# GEOF_MainBoard.net
KiCad netlist of a schematic drawn in EasyEDA Pro
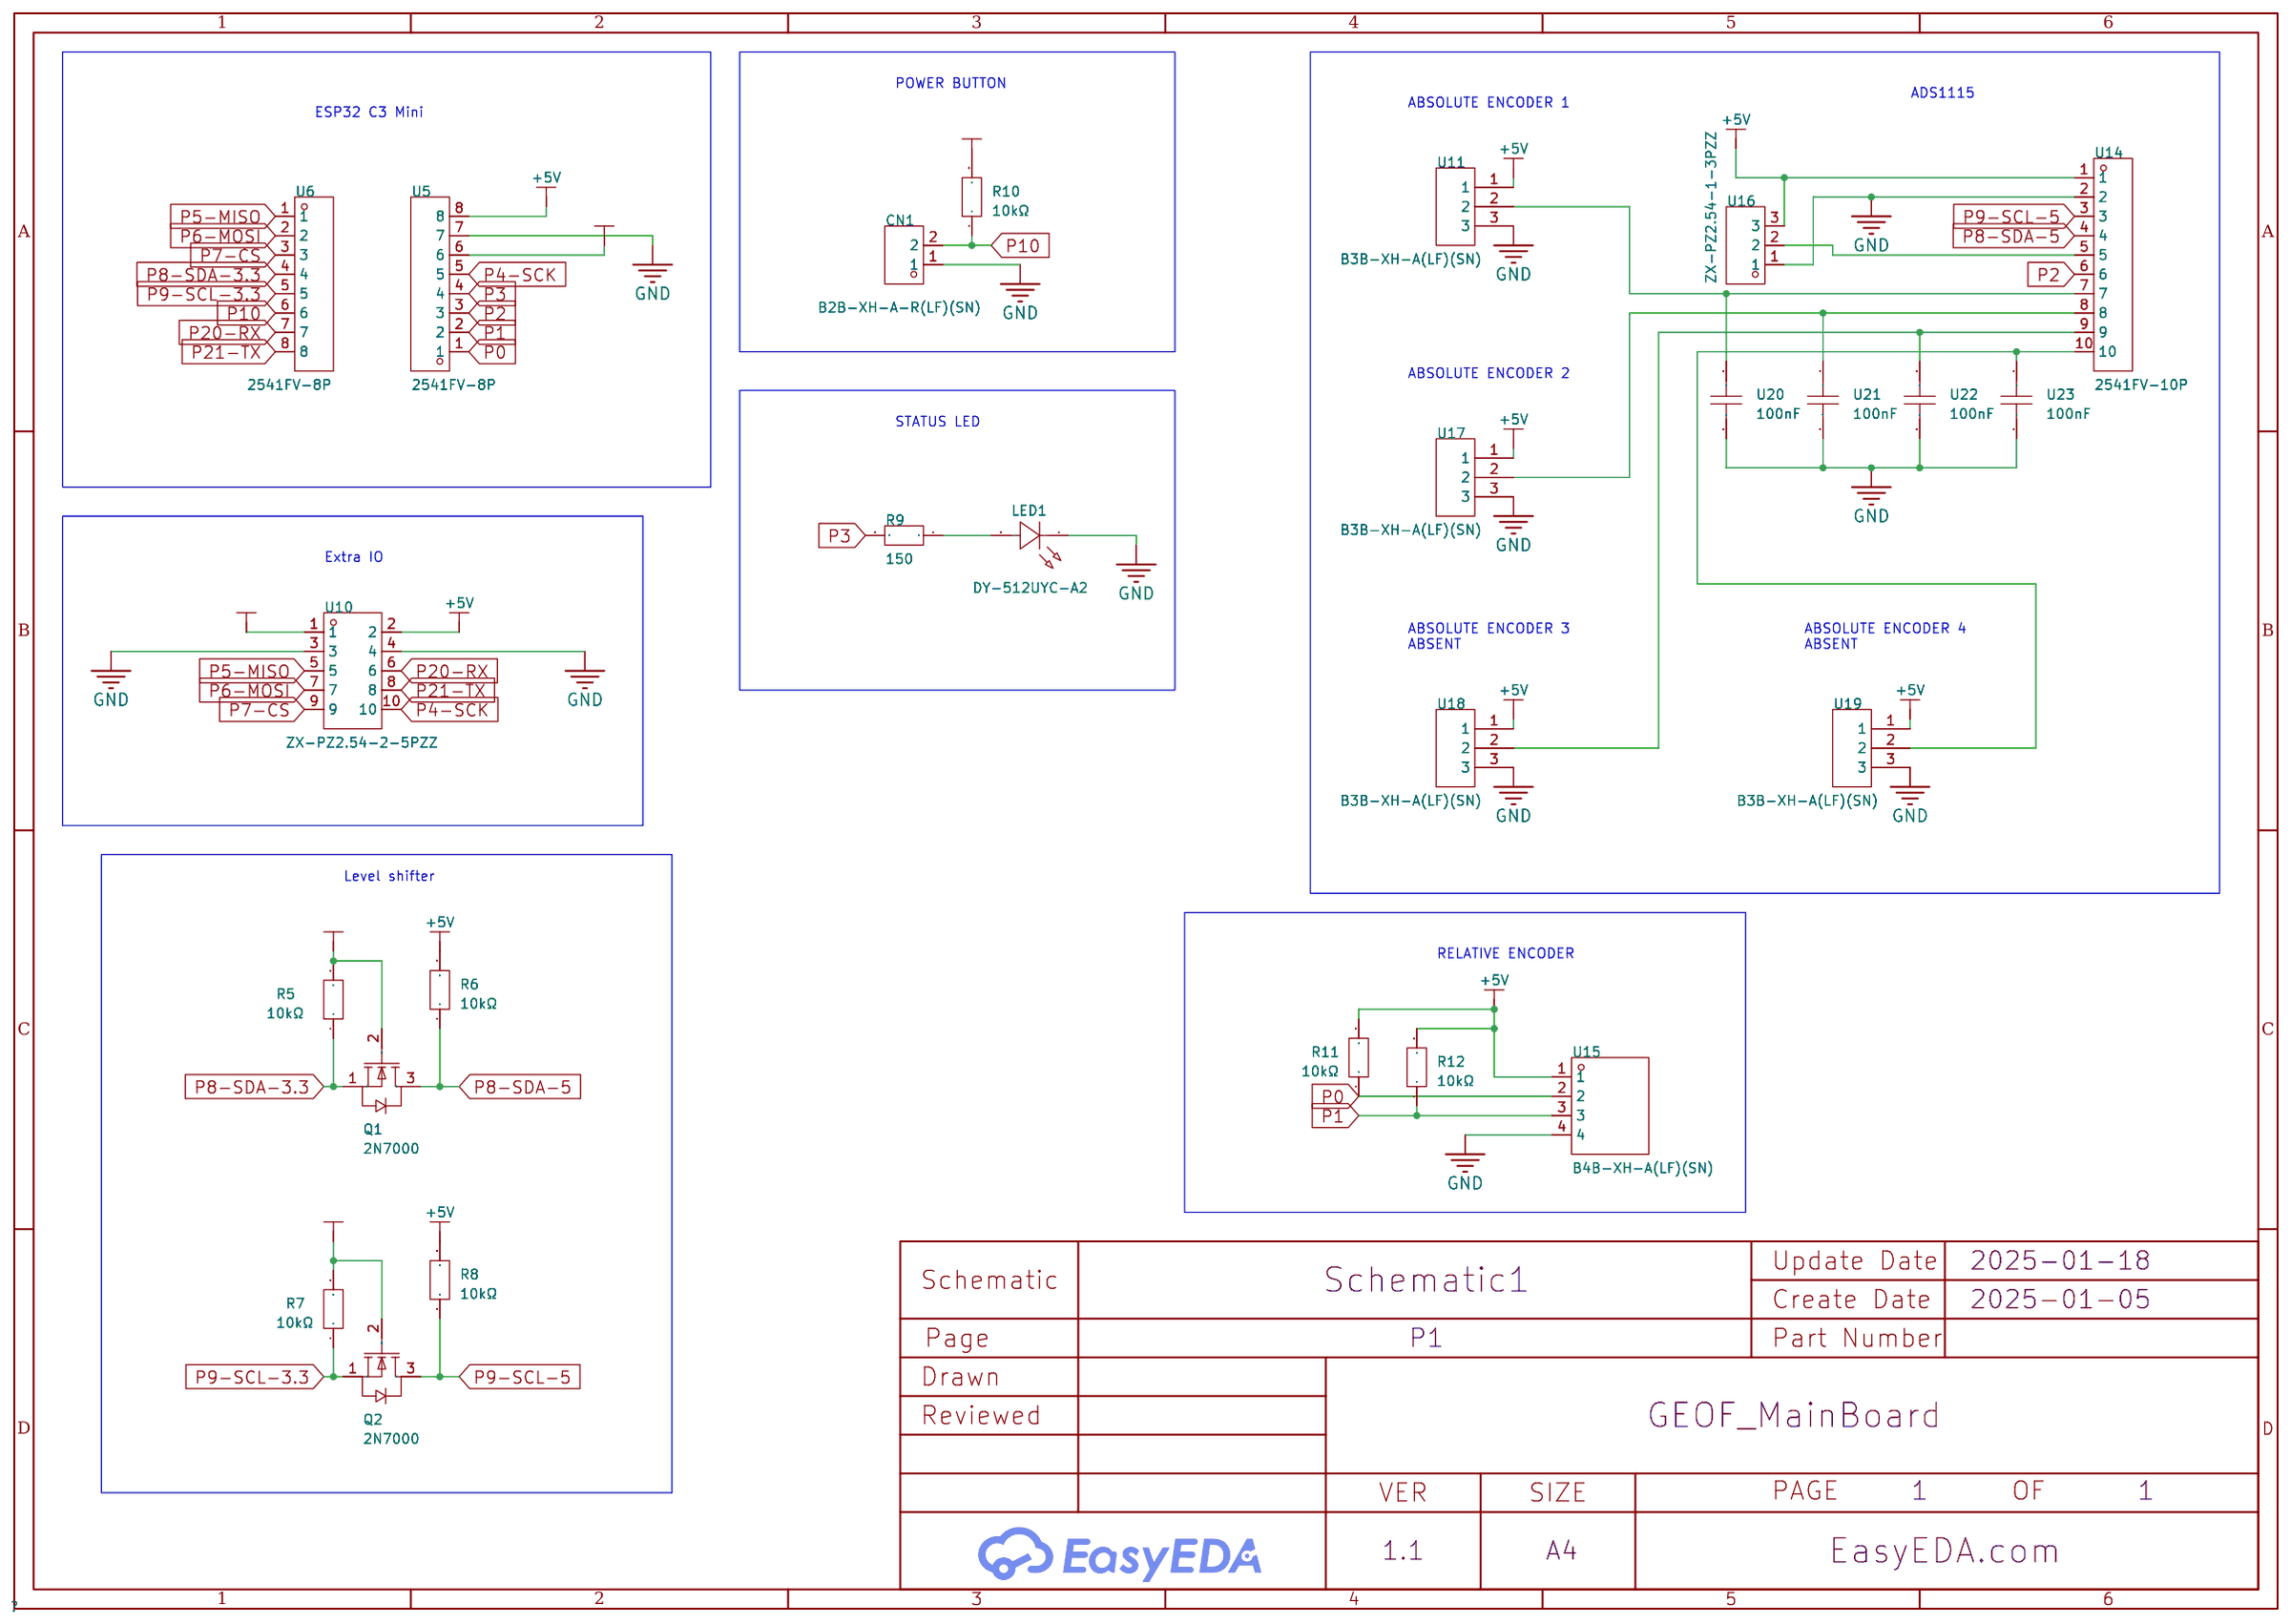
[diagram p0: schematic sheet]

(export (version "E")
  (design (tool "Eeschema 10.0.6"))
  (components
    (comp (ref "CN1")
      (value "B2B-XH-A-R(LF)(SN)")
      (footprint "easyedapro:CONN-TH_B2B-XH-A")
      (fields (field (name "Manufacturer") "JST"))
      (libsource (lib "easyedapro") (part "B2B-XH-A-R(LF)(SN)"))
    )
    (comp (ref "LED1")
      (value "DY-512UYC-A2")
      (footprint "easyedapro:LED-TH_L3.2-W2.0-P2.54-RD")
      (fields (field (name "Manufacturer") "TONYU(东裕)"))
      (libsource (lib "easyedapro") (part "DY-512UYC-A2"))
    )
    (comp (ref "Q1")
      (value "2N7000")
      (footprint "easyedapro:TO-92-3_L4.9-W3.7-P1.27-L")
      (fields (field (name "Manufacturer") "onsemi(安森美)"))
      (libsource (lib "easyedapro") (part "2N7000_C232838"))
    )
    (comp (ref "Q2")
      (value "2N7000")
      (footprint "easyedapro:TO-92-3_L4.9-W3.7-P1.27-L")
      (fields (field (name "Manufacturer") "onsemi(安森美)"))
      (libsource (lib "easyedapro") (part "2N7000_C232838"))
    )
    (comp (ref "R5")
      (value "10kΩ")
      (footprint "easyedapro:RES-TH_BD2.7-L6.2-P10.20-D0.4")
      (fields (field (name "Manufacturer Part") "MF1/4W-10K±1%-ST52") (field (name "Manufacturer") "VO(翔胜)"))
      (libsource (lib "easyedapro") (part "MF1/4W-10K±1%-ST52"))
    )
    (comp (ref "R6")
      (value "10kΩ")
      (footprint "easyedapro:RES-TH_BD2.7-L6.2-P10.20-D0.4")
      (fields (field (name "Manufacturer Part") "MF1/4W-10K±1%-ST52") (field (name "Manufacturer") "VO(翔胜)"))
      (libsource (lib "easyedapro") (part "MF1/4W-10K±1%-ST52"))
    )
    (comp (ref "R7")
      (value "10kΩ")
      (footprint "easyedapro:RES-TH_BD2.7-L6.2-P10.20-D0.4")
      (fields (field (name "Manufacturer Part") "MF1/4W-10K±1%-ST52") (field (name "Manufacturer") "VO(翔胜)"))
      (libsource (lib "easyedapro") (part "MF1/4W-10K±1%-ST52"))
    )
    (comp (ref "R8")
      (value "10kΩ")
      (footprint "easyedapro:RES-TH_BD2.7-L6.2-P10.20-D0.4")
      (fields (field (name "Manufacturer Part") "MF1/4W-10K±1%-ST52") (field (name "Manufacturer") "VO(翔胜)"))
      (libsource (lib "easyedapro") (part "MF1/4W-10K±1%-ST52"))
    )
    (comp (ref "R9")
      (value "150")
      (footprint "easyedapro:RES-TH_BD2.7-L6.2-P10.20-D0.4")
      (fields (field (name "Manufacturer Part") "MF1/4W-10K±1%-ST52") (field (name "Manufacturer") "VO(翔胜)"))
      (libsource (lib "easyedapro") (part "MF1/4W-10K±1%-ST52"))
    )
    (comp (ref "R10")
      (value "10kΩ")
      (footprint "easyedapro:RES-TH_BD2.7-L6.2-P10.20-D0.4")
      (fields (field (name "Manufacturer Part") "MF1/4W-10K±1%-ST52") (field (name "Manufacturer") "VO(翔胜)"))
      (libsource (lib "easyedapro") (part "MF1/4W-10K±1%-ST52"))
    )
    (comp (ref "R11")
      (value "10kΩ")
      (footprint "easyedapro:RES-TH_BD2.7-L6.2-P10.20-D0.4")
      (fields (field (name "Manufacturer Part") "MF1/4W-10K±1%-ST52") (field (name "Manufacturer") "VO(翔胜)"))
      (libsource (lib "easyedapro") (part "MF1/4W-10K±1%-ST52"))
    )
    (comp (ref "R12")
      (value "10kΩ")
      (footprint "easyedapro:RES-TH_BD2.7-L6.2-P10.20-D0.4")
      (fields (field (name "Manufacturer Part") "MF1/4W-10K±1%-ST52") (field (name "Manufacturer") "VO(翔胜)"))
      (libsource (lib "easyedapro") (part "MF1/4W-10K±1%-ST52"))
    )
    (comp (ref "U5")
      (value "2541FV-8P")
      (footprint "easyedapro:HDR-TH_8P-P2.54-V-F")
      (fields (field (name "Manufacturer") "HanElectricity(瀚源)"))
      (libsource (lib "easyedapro") (part "2541FV-8P"))
    )
    (comp (ref "U6")
      (value "2541FV-8P")
      (footprint "easyedapro:HDR-TH_8P-P2.54-V-F")
      (fields (field (name "Manufacturer") "HanElectricity(瀚源)"))
      (libsource (lib "easyedapro") (part "2541FV-8P"))
    )
    (comp (ref "U10")
      (value "ZX-PZ2.54-2-5PZZ")
      (footprint "easyedapro:HDR-TH_10P-P2.54-V-M-R2-C5-S2.54")
      (fields (field (name "Manufacturer") "Megastar(兆星)"))
      (libsource (lib "easyedapro") (part "ZX-PZ2.54-2-5PZZ"))
    )
    (comp (ref "U11")
      (value "B3B-XH-A(LF)(SN)")
      (footprint "easyedapro:CONN-TH_3P-P2.50_A2501WV2-3P")
      (fields (field (name "Manufacturer") "JST"))
      (libsource (lib "easyedapro") (part "B3B-XH-A(LF)(SN)"))
    )
    (comp (ref "U14")
      (value "2541FV-10P")
      (footprint "easyedapro:HDR-TH_10P-P2.54-V-F")
      (fields (field (name "Manufacturer") "HanElectricity(瀚源)"))
      (libsource (lib "easyedapro") (part "2541FV-10P"))
    )
    (comp (ref "U15")
      (value "B4B-XH-A(LF)(SN)")
      (footprint "easyedapro:CONN-TH_B4B-XH-A-LF-SN")
      (fields (field (name "Manufacturer") "JST"))
      (libsource (lib "easyedapro") (part "B4B-XH-A(LF)(SN)"))
    )
    (comp (ref "U16")
      (value "ZX-PZ2.54-1-3PZZ")
      (footprint "easyedapro:HDR-TH_3P-P2.54-V-M-1")
      (fields (field (name "Manufacturer") "Megastar(兆星)"))
      (libsource (lib "easyedapro") (part "ZX-PZ2.54-1-3PZZ"))
    )
    (comp (ref "U17")
      (value "B3B-XH-A(LF)(SN)")
      (footprint "easyedapro:CONN-TH_3P-P2.50_A2501WV2-3P")
      (fields (field (name "Manufacturer") "JST"))
      (libsource (lib "easyedapro") (part "B3B-XH-A(LF)(SN)"))
    )
    (comp (ref "U18")
      (value "B3B-XH-A(LF)(SN)")
      (footprint "easyedapro:CONN-TH_3P-P2.50_A2501WV2-3P")
      (fields (field (name "Manufacturer") "JST"))
      (libsource (lib "easyedapro") (part "B3B-XH-A(LF)(SN)"))
    )
    (comp (ref "U19")
      (value "B3B-XH-A(LF)(SN)")
      (footprint "easyedapro:CONN-TH_3P-P2.50_A2501WV2-3P")
      (fields (field (name "Manufacturer") "JST"))
      (libsource (lib "easyedapro") (part "B3B-XH-A(LF)(SN)"))
    )
    (comp (ref "U20")
      (value "100nF")
      (footprint "easyedapro:CAP-TH_L4.8-W2.4-P5.08-D0.6")
      (fields (field (name "Manufacturer Part") "178MU0013") (field (name "Manufacturer") "KNSCHA(科尼盛)"))
      (libsource (lib "easyedapro") (part "178MU0013"))
    )
    (comp (ref "U21")
      (value "100nF")
      (footprint "easyedapro:CAP-TH_L4.8-W2.4-P5.08-D0.6")
      (fields (field (name "Manufacturer Part") "178MU0013") (field (name "Manufacturer") "KNSCHA(科尼盛)"))
      (libsource (lib "easyedapro") (part "178MU0013"))
    )
    (comp (ref "U22")
      (value "100nF")
      (footprint "easyedapro:CAP-TH_L4.8-W2.4-P5.08-D0.6")
      (fields (field (name "Manufacturer Part") "178MU0013") (field (name "Manufacturer") "KNSCHA(科尼盛)"))
      (libsource (lib "easyedapro") (part "178MU0013"))
    )
    (comp (ref "U23")
      (value "100nF")
      (footprint "easyedapro:CAP-TH_L4.8-W2.4-P5.08-D0.6")
      (fields (field (name "Manufacturer Part") "178MU0013") (field (name "Manufacturer") "KNSCHA(科尼盛)"))
      (libsource (lib "easyedapro") (part "178MU0013"))
    )
  )
  (nets
    (net (code "1") (name "+3.3V") (class "Default")
      (node (ref "Q1") (pin "2") (pinfunction "G_2") (pintype "unspecified"))
      (node (ref "Q2") (pin "2") (pinfunction "G_2") (pintype "unspecified"))
      (node (ref "R10") (pin "2") (pinfunction "2_2") (pintype "unspecified"))
      (node (ref "R5") (pin "2") (pinfunction "2_2") (pintype "unspecified"))
      (node (ref "R7") (pin "2") (pinfunction "2_2") (pintype "unspecified"))
      (node (ref "U10") (pin "1") (pinfunction "1_1") (pintype "unspecified"))
      (node (ref "U5") (pin "6") (pinfunction "6_6") (pintype "unspecified"))
    )
    (net (code "2") (name "+5V") (class "Default")
      (node (ref "R11") (pin "2") (pinfunction "2_2") (pintype "unspecified"))
      (node (ref "R12") (pin "2") (pinfunction "2_2") (pintype "unspecified"))
      (node (ref "R6") (pin "2") (pinfunction "2_2") (pintype "unspecified"))
      (node (ref "R8") (pin "2") (pinfunction "2_2") (pintype "unspecified"))
      (node (ref "U10") (pin "2") (pinfunction "2_2") (pintype "unspecified"))
      (node (ref "U11") (pin "1") (pinfunction "1_1") (pintype "unspecified"))
      (node (ref "U14") (pin "1") (pinfunction "1_1") (pintype "unspecified"))
      (node (ref "U15") (pin "1") (pinfunction "1_1") (pintype "unspecified"))
      (node (ref "U16") (pin "3") (pinfunction "3_3") (pintype "unspecified"))
      (node (ref "U17") (pin "1") (pinfunction "1_1") (pintype "unspecified"))
      (node (ref "U18") (pin "1") (pinfunction "1_1") (pintype "unspecified"))
      (node (ref "U19") (pin "1") (pinfunction "1_1") (pintype "unspecified"))
      (node (ref "U5") (pin "8") (pinfunction "8_8") (pintype "unspecified"))
    )
    (net (code "3") (name "GND") (class "Default")
      (node (ref "CN1") (pin "1") (pinfunction "1_1") (pintype "unspecified"))
      (node (ref "LED1") (pin "1") (pinfunction "-_1") (pintype "unspecified"))
      (node (ref "U10") (pin "3") (pinfunction "3_3") (pintype "unspecified"))
      (node (ref "U10") (pin "4") (pinfunction "4_4") (pintype "unspecified"))
      (node (ref "U11") (pin "3") (pinfunction "3_3") (pintype "unspecified"))
      (node (ref "U14") (pin "2") (pinfunction "2_2") (pintype "unspecified"))
      (node (ref "U15") (pin "4") (pinfunction "4_4") (pintype "unspecified"))
      (node (ref "U16") (pin "1") (pinfunction "1_1") (pintype "unspecified"))
      (node (ref "U17") (pin "3") (pinfunction "3_3") (pintype "unspecified"))
      (node (ref "U18") (pin "3") (pinfunction "3_3") (pintype "unspecified"))
      (node (ref "U19") (pin "3") (pinfunction "3_3") (pintype "unspecified"))
      (node (ref "U20") (pin "2") (pinfunction "2_2") (pintype "unspecified"))
      (node (ref "U21") (pin "2") (pinfunction "2_2") (pintype "unspecified"))
      (node (ref "U22") (pin "2") (pinfunction "2_2") (pintype "unspecified"))
      (node (ref "U23") (pin "2") (pinfunction "2_2") (pintype "unspecified"))
      (node (ref "U5") (pin "7") (pinfunction "7_7") (pintype "unspecified"))
    )
    (net (code "4") (name "Net-(LED1-+)") (class "Default")
      (node (ref "LED1") (pin "2") (pinfunction "+_2") (pintype "unspecified"))
      (node (ref "R9") (pin "1") (pinfunction "1_1") (pintype "unspecified"))
    )
    (net (code "5") (name "Net-(U11-Pad2)") (class "Default")
      (node (ref "U11") (pin "2") (pinfunction "2_2") (pintype "unspecified"))
      (node (ref "U14") (pin "7") (pinfunction "7_7") (pintype "unspecified"))
      (node (ref "U20") (pin "1") (pinfunction "1_1") (pintype "unspecified"))
    )
    (net (code "6") (name "Net-(U14-Pad5)") (class "Default")
      (node (ref "U14") (pin "5") (pinfunction "5_5") (pintype "unspecified"))
      (node (ref "U16") (pin "2") (pinfunction "2_2") (pintype "unspecified"))
    )
    (net (code "7") (name "Net-(U14-Pad8)") (class "Default")
      (node (ref "U14") (pin "8") (pinfunction "8_8") (pintype "unspecified"))
      (node (ref "U17") (pin "2") (pinfunction "2_2") (pintype "unspecified"))
      (node (ref "U21") (pin "1") (pinfunction "1_1") (pintype "unspecified"))
    )
    (net (code "8") (name "Net-(U14-Pad9)") (class "Default")
      (node (ref "U14") (pin "9") (pinfunction "9_9") (pintype "unspecified"))
      (node (ref "U18") (pin "2") (pinfunction "2_2") (pintype "unspecified"))
      (node (ref "U22") (pin "1") (pinfunction "1_1") (pintype "unspecified"))
    )
    (net (code "9") (name "Net-(U14-Pad10)") (class "Default")
      (node (ref "U14") (pin "10") (pinfunction "10_10") (pintype "unspecified"))
      (node (ref "U19") (pin "2") (pinfunction "2_2") (pintype "unspecified"))
      (node (ref "U23") (pin "1") (pinfunction "1_1") (pintype "unspecified"))
    )
    (net (code "10") (name "P0") (class "Default")
      (node (ref "R11") (pin "1") (pinfunction "1_1") (pintype "unspecified"))
      (node (ref "U15") (pin "2") (pinfunction "2_2") (pintype "unspecified"))
      (node (ref "U5") (pin "1") (pinfunction "1_1") (pintype "unspecified"))
    )
    (net (code "11") (name "P1") (class "Default")
      (node (ref "R12") (pin "1") (pinfunction "1_1") (pintype "unspecified"))
      (node (ref "U15") (pin "3") (pinfunction "3_3") (pintype "unspecified"))
      (node (ref "U5") (pin "2") (pinfunction "2_2") (pintype "unspecified"))
    )
    (net (code "12") (name "P2") (class "Default")
      (node (ref "U14") (pin "6") (pinfunction "6_6") (pintype "unspecified"))
      (node (ref "U5") (pin "3") (pinfunction "3_3") (pintype "unspecified"))
    )
    (net (code "13") (name "P3") (class "Default")
      (node (ref "R9") (pin "2") (pinfunction "2_2") (pintype "unspecified"))
      (node (ref "U5") (pin "4") (pinfunction "4_4") (pintype "unspecified"))
    )
    (net (code "14") (name "P4-SCK") (class "Default")
      (node (ref "U10") (pin "10") (pinfunction "10_10") (pintype "unspecified"))
      (node (ref "U5") (pin "5") (pinfunction "5_5") (pintype "unspecified"))
    )
    (net (code "15") (name "P5-MISO") (class "Default")
      (node (ref "U10") (pin "5") (pinfunction "5_5") (pintype "unspecified"))
      (node (ref "U6") (pin "1") (pinfunction "1_1") (pintype "unspecified"))
    )
    (net (code "16") (name "P6-MOSI") (class "Default")
      (node (ref "U10") (pin "7") (pinfunction "7_7") (pintype "unspecified"))
      (node (ref "U6") (pin "2") (pinfunction "2_2") (pintype "unspecified"))
    )
    (net (code "17") (name "P7-CS") (class "Default")
      (node (ref "U10") (pin "9") (pinfunction "9_9") (pintype "unspecified"))
      (node (ref "U6") (pin "3") (pinfunction "3_3") (pintype "unspecified"))
    )
    (net (code "18") (name "P8-SDA-3.3") (class "Default")
      (node (ref "Q1") (pin "1") (pinfunction "S_1") (pintype "unspecified"))
      (node (ref "R5") (pin "1") (pinfunction "1_1") (pintype "unspecified"))
      (node (ref "U6") (pin "4") (pinfunction "4_4") (pintype "unspecified"))
    )
    (net (code "19") (name "P8-SDA-5") (class "Default")
      (node (ref "Q1") (pin "3") (pinfunction "D_3") (pintype "unspecified"))
      (node (ref "R6") (pin "1") (pinfunction "1_1") (pintype "unspecified"))
      (node (ref "U14") (pin "4") (pinfunction "4_4") (pintype "unspecified"))
    )
    (net (code "20") (name "P9-SCL-3.3") (class "Default")
      (node (ref "Q2") (pin "1") (pinfunction "S_1") (pintype "unspecified"))
      (node (ref "R7") (pin "1") (pinfunction "1_1") (pintype "unspecified"))
      (node (ref "U6") (pin "5") (pinfunction "5_5") (pintype "unspecified"))
    )
    (net (code "21") (name "P9-SCL-5") (class "Default")
      (node (ref "Q2") (pin "3") (pinfunction "D_3") (pintype "unspecified"))
      (node (ref "R8") (pin "1") (pinfunction "1_1") (pintype "unspecified"))
      (node (ref "U14") (pin "3") (pinfunction "3_3") (pintype "unspecified"))
    )
    (net (code "22") (name "P10") (class "Default")
      (node (ref "CN1") (pin "2") (pinfunction "2_2") (pintype "unspecified"))
      (node (ref "R10") (pin "1") (pinfunction "1_1") (pintype "unspecified"))
      (node (ref "U6") (pin "6") (pinfunction "6_6") (pintype "unspecified"))
    )
    (net (code "23") (name "P20-RX") (class "Default")
      (node (ref "U10") (pin "6") (pinfunction "6_6") (pintype "unspecified"))
      (node (ref "U6") (pin "7") (pinfunction "7_7") (pintype "unspecified"))
    )
    (net (code "24") (name "P21-TX") (class "Default")
      (node (ref "U10") (pin "8") (pinfunction "8_8") (pintype "unspecified"))
      (node (ref "U6") (pin "8") (pinfunction "8_8") (pintype "unspecified"))
    )
  )
)
